# mimic1579.net
KiCad netlist of a schematic drawn in EAGLE
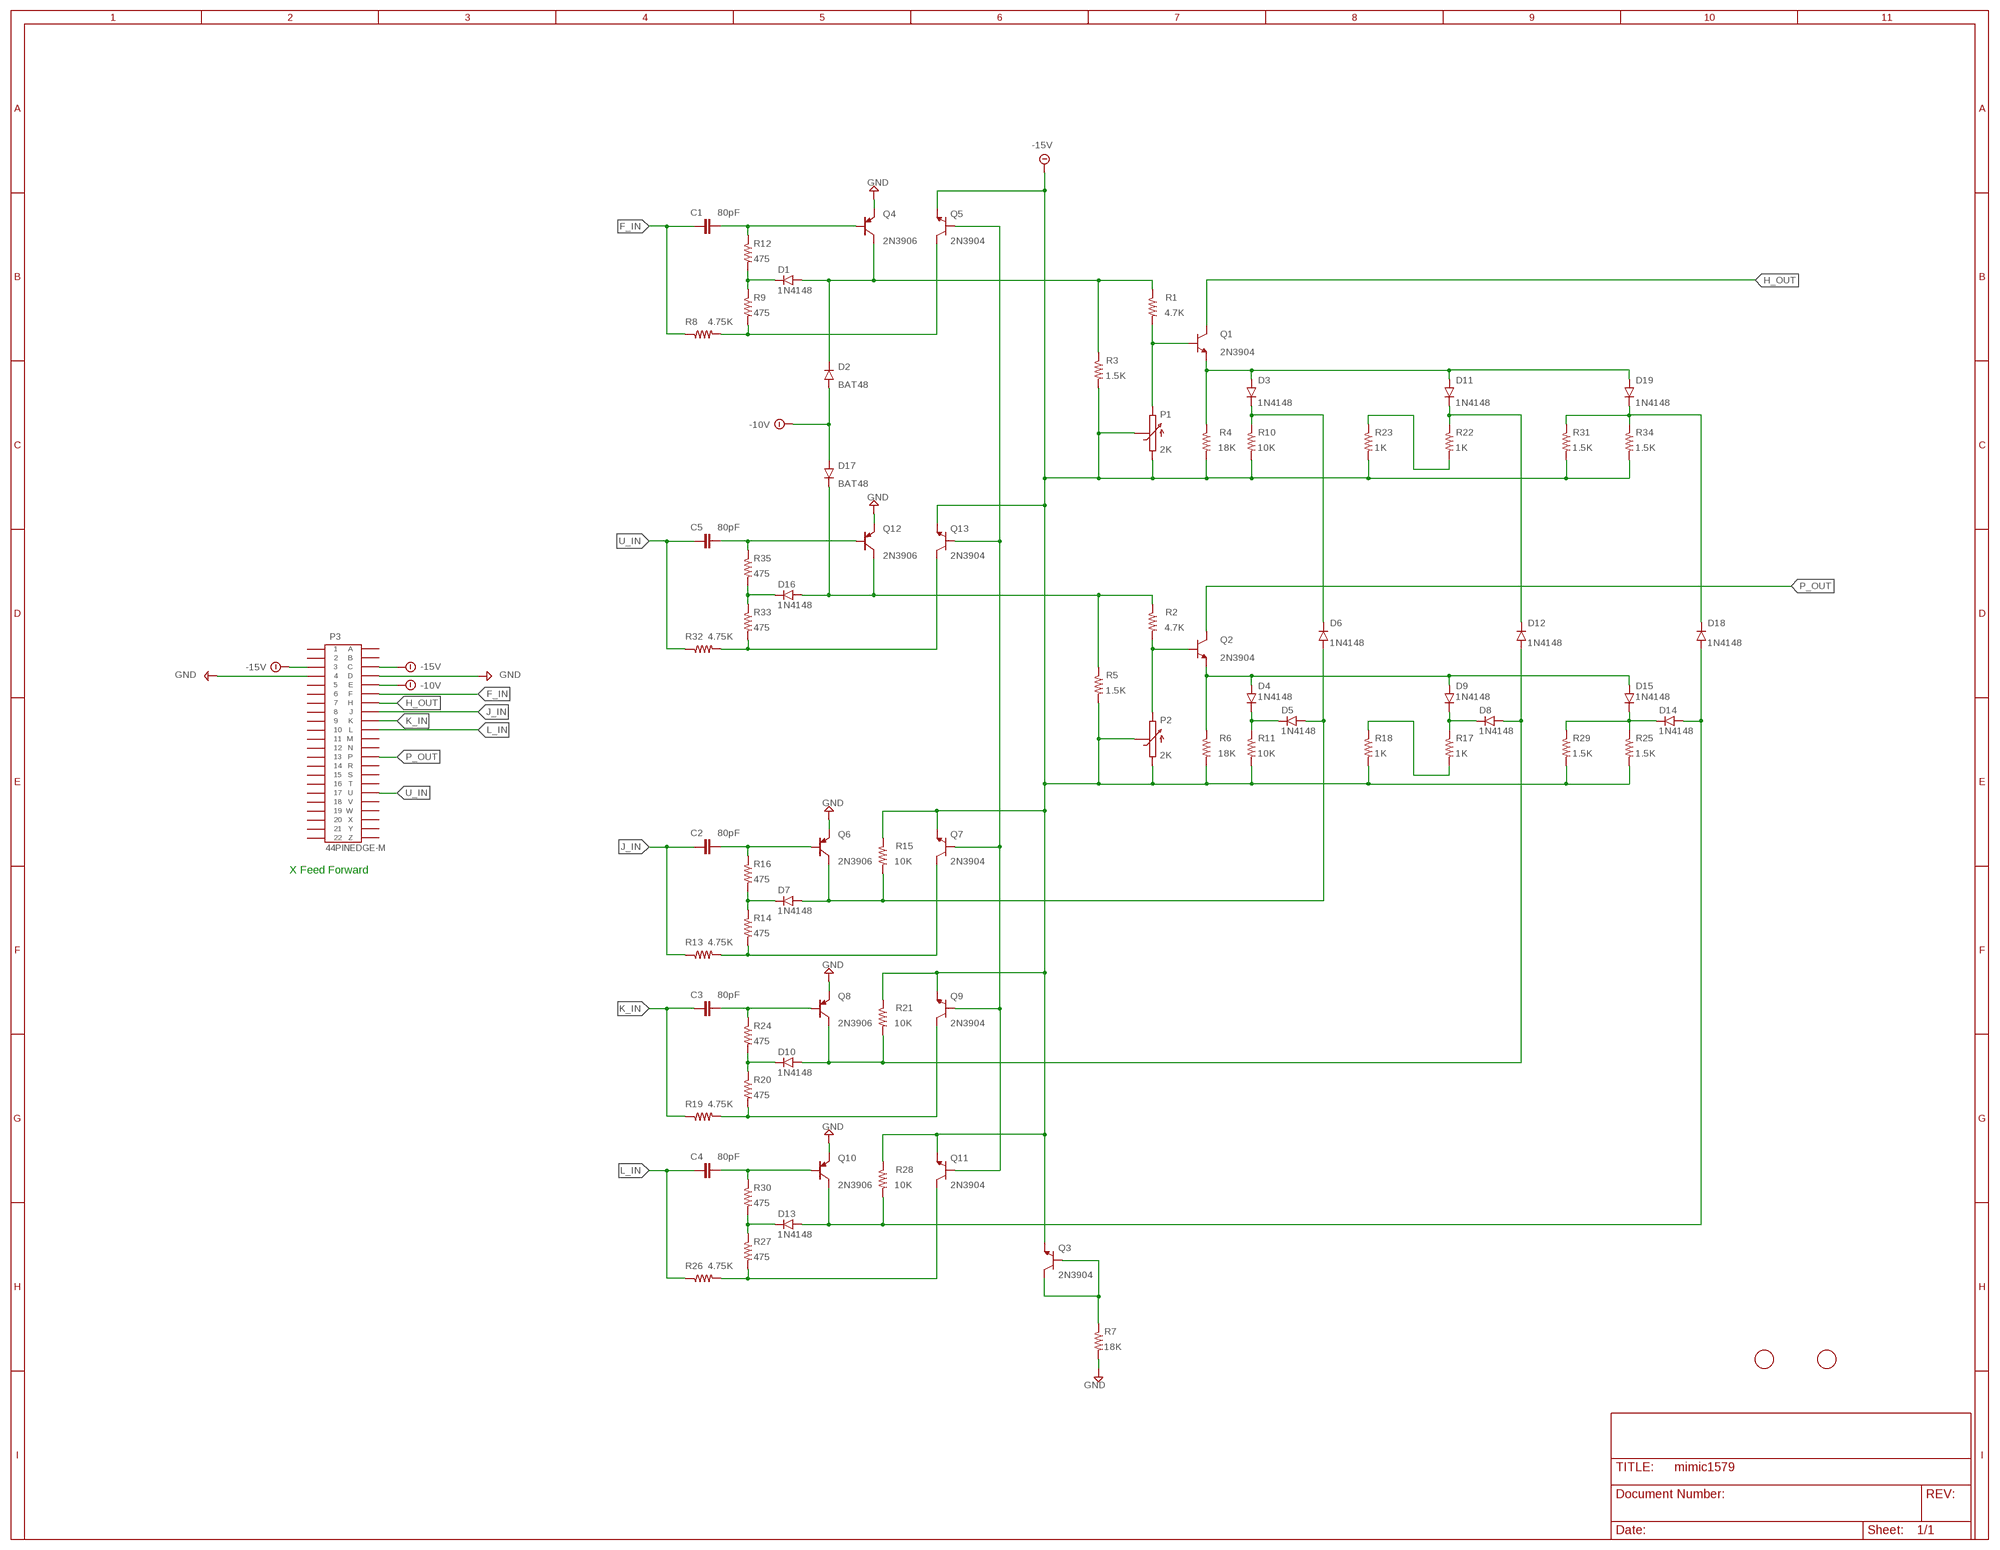
[diagram p0: schematic, sheet 1]

(export (version "E")
  (design (tool "Eeschema 10.0.6"))
  (components
    (comp (ref "C1")
      (value "80pF")
      (footprint "eagle-import:5MM_TH")
      (libsource (lib "eagle-import") (part "CAP80PF"))
    )
    (comp (ref "C2")
      (value "80pF")
      (footprint "eagle-import:5MM_TH")
      (libsource (lib "eagle-import") (part "CAP80PF"))
    )
    (comp (ref "C3")
      (value "80pF")
      (footprint "eagle-import:5MM_TH")
      (libsource (lib "eagle-import") (part "CAP80PF"))
    )
    (comp (ref "C4")
      (value "80pF")
      (footprint "eagle-import:5MM_TH")
      (libsource (lib "eagle-import") (part "CAP80PF"))
    )
    (comp (ref "C5")
      (value "80pF")
      (footprint "eagle-import:5MM_TH")
      (libsource (lib "eagle-import") (part "CAP80PF"))
    )
    (comp (ref "D1")
      (value "1N4148")
      (footprint "eagle-import:DO35-7")
      (libsource (lib "eagle-import") (part "1N4148"))
    )
    (comp (ref "D2")
      (value "BAT48")
      (footprint "eagle-import:DO35-7")
      (libsource (lib "eagle-import") (part "1N4148"))
    )
    (comp (ref "D3")
      (value "1N4148")
      (footprint "eagle-import:DO35-7")
      (libsource (lib "eagle-import") (part "1N4148"))
    )
    (comp (ref "D4")
      (value "1N4148")
      (footprint "eagle-import:DO35-7")
      (libsource (lib "eagle-import") (part "1N4148"))
    )
    (comp (ref "D5")
      (value "1N4148")
      (footprint "eagle-import:DO35-7")
      (libsource (lib "eagle-import") (part "1N4148"))
    )
    (comp (ref "D6")
      (value "1N4148")
      (footprint "eagle-import:DO35-7")
      (libsource (lib "eagle-import") (part "1N4148"))
    )
    (comp (ref "D7")
      (value "1N4148")
      (footprint "eagle-import:DO35-7")
      (libsource (lib "eagle-import") (part "1N4148"))
    )
    (comp (ref "D8")
      (value "1N4148")
      (footprint "eagle-import:DO35-7")
      (libsource (lib "eagle-import") (part "1N4148"))
    )
    (comp (ref "D9")
      (value "1N4148")
      (footprint "eagle-import:DO35-7")
      (libsource (lib "eagle-import") (part "1N4148"))
    )
    (comp (ref "D10")
      (value "1N4148")
      (footprint "eagle-import:DO35-7")
      (libsource (lib "eagle-import") (part "1N4148"))
    )
    (comp (ref "D11")
      (value "1N4148")
      (footprint "eagle-import:DO35-7")
      (libsource (lib "eagle-import") (part "1N4148"))
    )
    (comp (ref "D12")
      (value "1N4148")
      (footprint "eagle-import:DO35-7")
      (libsource (lib "eagle-import") (part "1N4148"))
    )
    (comp (ref "D13")
      (value "1N4148")
      (footprint "eagle-import:DO35-7")
      (libsource (lib "eagle-import") (part "1N4148"))
    )
    (comp (ref "D14")
      (value "1N4148")
      (footprint "eagle-import:DO35-7")
      (libsource (lib "eagle-import") (part "1N4148"))
    )
    (comp (ref "D15")
      (value "1N4148")
      (footprint "eagle-import:DO35-7")
      (libsource (lib "eagle-import") (part "1N4148"))
    )
    (comp (ref "D16")
      (value "1N4148")
      (footprint "eagle-import:DO35-7")
      (libsource (lib "eagle-import") (part "1N4148"))
    )
    (comp (ref "D17")
      (value "BAT48")
      (footprint "eagle-import:DO35-7")
      (libsource (lib "eagle-import") (part "1N4148"))
    )
    (comp (ref "D18")
      (value "1N4148")
      (footprint "eagle-import:DO35-7")
      (libsource (lib "eagle-import") (part "1N4148"))
    )
    (comp (ref "D19")
      (value "1N4148")
      (footprint "eagle-import:DO35-7")
      (libsource (lib "eagle-import") (part "1N4148"))
    )
    (comp (ref "P1")
      (value "2K")
      (footprint "eagle-import:3006P")
      (libsource (lib "eagle-import") (part "POT-3006P"))
    )
    (comp (ref "P2")
      (value "2K")
      (footprint "eagle-import:3006P")
      (libsource (lib "eagle-import") (part "POT-3006P"))
    )
    (comp (ref "P3")
      (value "44PINEDGE-M")
      (footprint "eagle-import:44PINEDGE")
      (libsource (lib "eagle-import") (part "44PINEDGE-M"))
    )
    (comp (ref "Q1")
      (value "2N3904")
      (footprint "eagle-import:TO92")
      (libsource (lib "eagle-import") (part "2N3904"))
    )
    (comp (ref "Q2")
      (value "2N3904")
      (footprint "eagle-import:TO92")
      (libsource (lib "eagle-import") (part "2N3904"))
    )
    (comp (ref "Q3")
      (value "2N3904")
      (footprint "eagle-import:TO92")
      (libsource (lib "eagle-import") (part "2N3904"))
    )
    (comp (ref "Q4")
      (value "2N3906")
      (footprint "eagle-import:TO92")
      (libsource (lib "eagle-import") (part "2N3906"))
    )
    (comp (ref "Q5")
      (value "2N3904")
      (footprint "eagle-import:TO92")
      (libsource (lib "eagle-import") (part "2N3904"))
    )
    (comp (ref "Q6")
      (value "2N3906")
      (footprint "eagle-import:TO92")
      (libsource (lib "eagle-import") (part "2N3906"))
    )
    (comp (ref "Q7")
      (value "2N3904")
      (footprint "eagle-import:TO92")
      (libsource (lib "eagle-import") (part "2N3904"))
    )
    (comp (ref "Q8")
      (value "2N3906")
      (footprint "eagle-import:TO92")
      (libsource (lib "eagle-import") (part "2N3906"))
    )
    (comp (ref "Q9")
      (value "2N3904")
      (footprint "eagle-import:TO92")
      (libsource (lib "eagle-import") (part "2N3904"))
    )
    (comp (ref "Q10")
      (value "2N3906")
      (footprint "eagle-import:TO92")
      (libsource (lib "eagle-import") (part "2N3906"))
    )
    (comp (ref "Q11")
      (value "2N3904")
      (footprint "eagle-import:TO92")
      (libsource (lib "eagle-import") (part "2N3904"))
    )
    (comp (ref "Q12")
      (value "2N3906")
      (footprint "eagle-import:TO92")
      (libsource (lib "eagle-import") (part "2N3906"))
    )
    (comp (ref "Q13")
      (value "2N3904")
      (footprint "eagle-import:TO92")
      (libsource (lib "eagle-import") (part "2N3904"))
    )
    (comp (ref "R1")
      (value "4.7K")
      (footprint "eagle-import:0207_10")
      (libsource (lib "eagle-import") (part "R-1/4WATT"))
    )
    (comp (ref "R2")
      (value "4.7K")
      (footprint "eagle-import:0207_10")
      (libsource (lib "eagle-import") (part "R-1/4WATT"))
    )
    (comp (ref "R3")
      (value "1.5K")
      (footprint "eagle-import:0207_10")
      (libsource (lib "eagle-import") (part "R-1/4WATT"))
    )
    (comp (ref "R4")
      (value "18K")
      (footprint "eagle-import:0207_10")
      (libsource (lib "eagle-import") (part "R-1/4WATT"))
    )
    (comp (ref "R5")
      (value "1.5K")
      (footprint "eagle-import:0207_10")
      (libsource (lib "eagle-import") (part "R-1/4WATT"))
    )
    (comp (ref "R6")
      (value "18K")
      (footprint "eagle-import:0207_10")
      (libsource (lib "eagle-import") (part "R-1/4WATT"))
    )
    (comp (ref "R7")
      (value "18K")
      (footprint "eagle-import:0207_10")
      (libsource (lib "eagle-import") (part "R-1/4WATT"))
    )
    (comp (ref "R8")
      (value "4.75K")
      (footprint "eagle-import:0207_10")
      (libsource (lib "eagle-import") (part "R-1/4WATT"))
    )
    (comp (ref "R9")
      (value "475")
      (footprint "eagle-import:0207_10")
      (libsource (lib "eagle-import") (part "R-1/4WATT"))
    )
    (comp (ref "R10")
      (value "10K")
      (footprint "eagle-import:0207_10")
      (libsource (lib "eagle-import") (part "R-1/4WATT"))
    )
    (comp (ref "R11")
      (value "10K")
      (footprint "eagle-import:0207_10")
      (libsource (lib "eagle-import") (part "R-1/4WATT"))
    )
    (comp (ref "R12")
      (value "475")
      (footprint "eagle-import:0207_10")
      (libsource (lib "eagle-import") (part "R-1/4WATT"))
    )
    (comp (ref "R13")
      (value "4.75K")
      (footprint "eagle-import:0207_10")
      (libsource (lib "eagle-import") (part "R-1/4WATT"))
    )
    (comp (ref "R14")
      (value "475")
      (footprint "eagle-import:0207_10")
      (libsource (lib "eagle-import") (part "R-1/4WATT"))
    )
    (comp (ref "R15")
      (value "10K")
      (footprint "eagle-import:0207_10")
      (libsource (lib "eagle-import") (part "R-1/4WATT"))
    )
    (comp (ref "R16")
      (value "475")
      (footprint "eagle-import:0207_10")
      (libsource (lib "eagle-import") (part "R-1/4WATT"))
    )
    (comp (ref "R17")
      (value "1K")
      (footprint "eagle-import:0207_10")
      (libsource (lib "eagle-import") (part "R-1/4WATT"))
    )
    (comp (ref "R18")
      (value "1K")
      (footprint "eagle-import:0207_10")
      (libsource (lib "eagle-import") (part "R-1/4WATT"))
    )
    (comp (ref "R19")
      (value "4.75K")
      (footprint "eagle-import:0207_10")
      (libsource (lib "eagle-import") (part "R-1/4WATT"))
    )
    (comp (ref "R20")
      (value "475")
      (footprint "eagle-import:0207_10")
      (libsource (lib "eagle-import") (part "R-1/4WATT"))
    )
    (comp (ref "R21")
      (value "10K")
      (footprint "eagle-import:0207_10")
      (libsource (lib "eagle-import") (part "R-1/4WATT"))
    )
    (comp (ref "R22")
      (value "1K")
      (footprint "eagle-import:0207_10")
      (libsource (lib "eagle-import") (part "R-1/4WATT"))
    )
    (comp (ref "R23")
      (value "1K")
      (footprint "eagle-import:0207_10")
      (libsource (lib "eagle-import") (part "R-1/4WATT"))
    )
    (comp (ref "R24")
      (value "475")
      (footprint "eagle-import:0207_10")
      (libsource (lib "eagle-import") (part "R-1/4WATT"))
    )
    (comp (ref "R25")
      (value "1.5K")
      (footprint "eagle-import:0207_10")
      (libsource (lib "eagle-import") (part "R-1/4WATT"))
    )
    (comp (ref "R26")
      (value "4.75K")
      (footprint "eagle-import:0207_10")
      (libsource (lib "eagle-import") (part "R-1/4WATT"))
    )
    (comp (ref "R27")
      (value "475")
      (footprint "eagle-import:0207_10")
      (libsource (lib "eagle-import") (part "R-1/4WATT"))
    )
    (comp (ref "R28")
      (value "10K")
      (footprint "eagle-import:0207_10")
      (libsource (lib "eagle-import") (part "R-1/4WATT"))
    )
    (comp (ref "R29")
      (value "1.5K")
      (footprint "eagle-import:0207_10")
      (libsource (lib "eagle-import") (part "R-1/4WATT"))
    )
    (comp (ref "R30")
      (value "475")
      (footprint "eagle-import:0207_10")
      (libsource (lib "eagle-import") (part "R-1/4WATT"))
    )
    (comp (ref "R31")
      (value "1.5K")
      (footprint "eagle-import:0207_10")
      (libsource (lib "eagle-import") (part "R-1/4WATT"))
    )
    (comp (ref "R32")
      (value "4.75K")
      (footprint "eagle-import:0207_10")
      (libsource (lib "eagle-import") (part "R-1/4WATT"))
    )
    (comp (ref "R33")
      (value "475")
      (footprint "eagle-import:0207_10")
      (libsource (lib "eagle-import") (part "R-1/4WATT"))
    )
    (comp (ref "R34")
      (value "1.5K")
      (footprint "eagle-import:0207_10")
      (libsource (lib "eagle-import") (part "R-1/4WATT"))
    )
    (comp (ref "R35")
      (value "475")
      (footprint "eagle-import:0207_10")
      (libsource (lib "eagle-import") (part "R-1/4WATT"))
    )
    (comp (ref "U$1")
      (value "FIDUCIAL")
      (footprint "eagle-import:FIDUCIAL_1MM")
      (libsource (lib "eagle-import") (part "FIDUCIAL"))
    )
    (comp (ref "U$2")
      (value "FIDUCIAL")
      (footprint "eagle-import:FIDUCIAL_1MM")
      (libsource (lib "eagle-import") (part "FIDUCIAL"))
    )
  )
  (nets
    (net (code "1") (name "-10V") (class "Default")
      (node (ref "D17") (pin "A") (pinfunction "A_A") (pintype "passive"))
      (node (ref "D2") (pin "A") (pinfunction "A_A") (pintype "passive"))
      (node (ref "P3") (pin "E") (pinfunction "E_E") (pintype "passive"))
    )
    (net (code "2") (name "-15V") (class "Default")
      (node (ref "P1") (pin "1") (pinfunction "1_1") (pintype "passive"))
      (node (ref "P1") (pin "2") (pinfunction "2_2") (pintype "passive"))
      (node (ref "P2") (pin "1") (pinfunction "1_1") (pintype "passive"))
      (node (ref "P2") (pin "2") (pinfunction "2_2") (pintype "passive"))
      (node (ref "P3") (pin "3") (pinfunction "3_3") (pintype "passive"))
      (node (ref "P3") (pin "C") (pinfunction "C_C") (pintype "passive"))
      (node (ref "Q11") (pin "1") (pinfunction "E_1") (pintype "passive"))
      (node (ref "Q13") (pin "1") (pinfunction "E_1") (pintype "passive"))
      (node (ref "Q3") (pin "1") (pinfunction "E_1") (pintype "passive"))
      (node (ref "Q5") (pin "1") (pinfunction "E_1") (pintype "passive"))
      (node (ref "Q7") (pin "1") (pinfunction "E_1") (pintype "passive"))
      (node (ref "Q9") (pin "1") (pinfunction "E_1") (pintype "passive"))
      (node (ref "R10") (pin "2") (pinfunction "P$2_2") (pintype "passive"))
      (node (ref "R11") (pin "2") (pinfunction "P$2_2") (pintype "passive"))
      (node (ref "R15") (pin "1") (pinfunction "P$1_1") (pintype "passive"))
      (node (ref "R18") (pin "2") (pinfunction "P$2_2") (pintype "passive"))
      (node (ref "R21") (pin "1") (pinfunction "P$1_1") (pintype "passive"))
      (node (ref "R23") (pin "2") (pinfunction "P$2_2") (pintype "passive"))
      (node (ref "R25") (pin "2") (pinfunction "P$2_2") (pintype "passive"))
      (node (ref "R28") (pin "1") (pinfunction "P$1_1") (pintype "passive"))
      (node (ref "R29") (pin "2") (pinfunction "P$2_2") (pintype "passive"))
      (node (ref "R3") (pin "2") (pinfunction "P$2_2") (pintype "passive"))
      (node (ref "R31") (pin "2") (pinfunction "P$2_2") (pintype "passive"))
      (node (ref "R34") (pin "2") (pinfunction "P$2_2") (pintype "passive"))
      (node (ref "R4") (pin "2") (pinfunction "P$2_2") (pintype "passive"))
      (node (ref "R5") (pin "2") (pinfunction "P$2_2") (pintype "passive"))
      (node (ref "R6") (pin "2") (pinfunction "P$2_2") (pintype "passive"))
    )
    (net (code "3") (name "F_IN") (class "Default")
      (node (ref "C1") (pin "1") (pinfunction "1_1") (pintype "passive"))
      (node (ref "P3") (pin "F") (pinfunction "F_F") (pintype "passive"))
      (node (ref "R8") (pin "1") (pinfunction "P$1_1") (pintype "passive"))
    )
    (net (code "4") (name "GND") (class "Default")
      (node (ref "P3") (pin "4") (pinfunction "4_4") (pintype "passive"))
      (node (ref "P3") (pin "D") (pinfunction "D_D") (pintype "passive"))
      (node (ref "Q10") (pin "3") (pinfunction "E_3") (pintype "passive"))
      (node (ref "Q12") (pin "3") (pinfunction "E_3") (pintype "passive"))
      (node (ref "Q4") (pin "3") (pinfunction "E_3") (pintype "passive"))
      (node (ref "Q6") (pin "3") (pinfunction "E_3") (pintype "passive"))
      (node (ref "Q8") (pin "3") (pinfunction "E_3") (pintype "passive"))
      (node (ref "R7") (pin "2") (pinfunction "P$2_2") (pintype "passive"))
    )
    (net (code "5") (name "H_OUT") (class "Default")
      (node (ref "P3") (pin "H") (pinfunction "H_H") (pintype "passive"))
      (node (ref "Q1") (pin "3") (pinfunction "C_3") (pintype "passive"))
    )
    (net (code "6") (name "J_IN") (class "Default")
      (node (ref "C2") (pin "1") (pinfunction "1_1") (pintype "passive"))
      (node (ref "P3") (pin "J") (pinfunction "J_J") (pintype "passive"))
      (node (ref "R13") (pin "1") (pinfunction "P$1_1") (pintype "passive"))
    )
    (net (code "7") (name "K_IN") (class "Default")
      (node (ref "C3") (pin "1") (pinfunction "1_1") (pintype "passive"))
      (node (ref "P3") (pin "K") (pinfunction "K_K") (pintype "passive"))
      (node (ref "R19") (pin "1") (pinfunction "P$1_1") (pintype "passive"))
    )
    (net (code "8") (name "L_IN") (class "Default")
      (node (ref "C4") (pin "1") (pinfunction "1_1") (pintype "passive"))
      (node (ref "P3") (pin "L") (pinfunction "L_L") (pintype "passive"))
      (node (ref "R26") (pin "1") (pinfunction "P$1_1") (pintype "passive"))
    )
    (net (code "9") (name "Net-(Q1-B)") (class "Default")
      (node (ref "P1") (pin "3") (pinfunction "3_3") (pintype "passive"))
      (node (ref "Q1") (pin "2") (pinfunction "B_2") (pintype "passive"))
      (node (ref "R1") (pin "2") (pinfunction "P$2_2") (pintype "passive"))
    )
    (net (code "10") (name "Net-(Q1-E)") (class "Default")
      (node (ref "D11") (pin "A") (pinfunction "A_A") (pintype "passive"))
      (node (ref "D19") (pin "A") (pinfunction "A_A") (pintype "passive"))
      (node (ref "D3") (pin "A") (pinfunction "A_A") (pintype "passive"))
      (node (ref "Q1") (pin "1") (pinfunction "E_1") (pintype "passive"))
      (node (ref "R4") (pin "1") (pinfunction "P$1_1") (pintype "passive"))
    )
    (net (code "11") (name "Net-(Q2-B)") (class "Default")
      (node (ref "P2") (pin "3") (pinfunction "3_3") (pintype "passive"))
      (node (ref "Q2") (pin "2") (pinfunction "B_2") (pintype "passive"))
      (node (ref "R2") (pin "2") (pinfunction "P$2_2") (pintype "passive"))
    )
    (net (code "12") (name "Net-(Q2-E)") (class "Default")
      (node (ref "D15") (pin "A") (pinfunction "A_A") (pintype "passive"))
      (node (ref "D4") (pin "A") (pinfunction "A_A") (pintype "passive"))
      (node (ref "D9") (pin "A") (pinfunction "A_A") (pintype "passive"))
      (node (ref "Q2") (pin "1") (pinfunction "E_1") (pintype "passive"))
      (node (ref "R6") (pin "1") (pinfunction "P$1_1") (pintype "passive"))
    )
    (net (code "13") (name "Net-(Q3-B)") (class "Default")
      (node (ref "Q3") (pin "2") (pinfunction "B_2") (pintype "passive"))
      (node (ref "Q3") (pin "3") (pinfunction "C_3") (pintype "passive"))
      (node (ref "R7") (pin "1") (pinfunction "P$1_1") (pintype "passive"))
    )
    (net (code "14") (name "Net-(Q4-B)") (class "Default")
      (node (ref "C1") (pin "2") (pinfunction "2_2") (pintype "passive"))
      (node (ref "Q4") (pin "2") (pinfunction "B_2") (pintype "passive"))
      (node (ref "R12") (pin "1") (pinfunction "P$1_1") (pintype "passive"))
    )
    (net (code "15") (name "Net-(Q4-C)") (class "Default")
      (node (ref "D1") (pin "A") (pinfunction "A_A") (pintype "passive"))
      (node (ref "D2") (pin "C") (pinfunction "C_C") (pintype "passive"))
      (node (ref "Q4") (pin "1") (pinfunction "C_1") (pintype "passive"))
      (node (ref "R1") (pin "1") (pinfunction "P$1_1") (pintype "passive"))
      (node (ref "R3") (pin "1") (pinfunction "P$1_1") (pintype "passive"))
    )
    (net (code "16") (name "Net-(Q5-C)") (class "Default")
      (node (ref "Q5") (pin "3") (pinfunction "C_3") (pintype "passive"))
      (node (ref "R8") (pin "2") (pinfunction "P$2_2") (pintype "passive"))
      (node (ref "R9") (pin "2") (pinfunction "P$2_2") (pintype "passive"))
    )
    (net (code "17") (name "Net-(Q6-B)") (class "Default")
      (node (ref "C2") (pin "2") (pinfunction "2_2") (pintype "passive"))
      (node (ref "Q6") (pin "2") (pinfunction "B_2") (pintype "passive"))
      (node (ref "R16") (pin "1") (pinfunction "P$1_1") (pintype "passive"))
    )
    (net (code "18") (name "Net-(Q6-C)") (class "Default")
      (node (ref "D5") (pin "A") (pinfunction "A_A") (pintype "passive"))
      (node (ref "D6") (pin "A") (pinfunction "A_A") (pintype "passive"))
      (node (ref "D7") (pin "A") (pinfunction "A_A") (pintype "passive"))
      (node (ref "Q6") (pin "1") (pinfunction "C_1") (pintype "passive"))
      (node (ref "R15") (pin "2") (pinfunction "P$2_2") (pintype "passive"))
    )
    (net (code "19") (name "Net-(Q7-C)") (class "Default")
      (node (ref "Q7") (pin "3") (pinfunction "C_3") (pintype "passive"))
      (node (ref "R13") (pin "2") (pinfunction "P$2_2") (pintype "passive"))
      (node (ref "R14") (pin "2") (pinfunction "P$2_2") (pintype "passive"))
    )
    (net (code "20") (name "Net-(Q8-B)") (class "Default")
      (node (ref "C3") (pin "2") (pinfunction "2_2") (pintype "passive"))
      (node (ref "Q8") (pin "2") (pinfunction "B_2") (pintype "passive"))
      (node (ref "R24") (pin "1") (pinfunction "P$1_1") (pintype "passive"))
    )
    (net (code "21") (name "Net-(Q8-C)") (class "Default")
      (node (ref "D10") (pin "A") (pinfunction "A_A") (pintype "passive"))
      (node (ref "D12") (pin "A") (pinfunction "A_A") (pintype "passive"))
      (node (ref "D8") (pin "A") (pinfunction "A_A") (pintype "passive"))
      (node (ref "Q8") (pin "1") (pinfunction "C_1") (pintype "passive"))
      (node (ref "R21") (pin "2") (pinfunction "P$2_2") (pintype "passive"))
    )
    (net (code "22") (name "Net-(Q9-C)") (class "Default")
      (node (ref "Q9") (pin "3") (pinfunction "C_3") (pintype "passive"))
      (node (ref "R19") (pin "2") (pinfunction "P$2_2") (pintype "passive"))
      (node (ref "R20") (pin "2") (pinfunction "P$2_2") (pintype "passive"))
    )
    (net (code "23") (name "Net-(Q10-B)") (class "Default")
      (node (ref "C4") (pin "2") (pinfunction "2_2") (pintype "passive"))
      (node (ref "Q10") (pin "2") (pinfunction "B_2") (pintype "passive"))
      (node (ref "R30") (pin "1") (pinfunction "P$1_1") (pintype "passive"))
    )
    (net (code "24") (name "Net-(Q10-C)") (class "Default")
      (node (ref "D13") (pin "A") (pinfunction "A_A") (pintype "passive"))
      (node (ref "D14") (pin "A") (pinfunction "A_A") (pintype "passive"))
      (node (ref "D18") (pin "A") (pinfunction "A_A") (pintype "passive"))
      (node (ref "Q10") (pin "1") (pinfunction "C_1") (pintype "passive"))
      (node (ref "R28") (pin "2") (pinfunction "P$2_2") (pintype "passive"))
    )
    (net (code "25") (name "Net-(Q11-B)") (class "Default")
      (node (ref "Q11") (pin "2") (pinfunction "B_2") (pintype "passive"))
      (node (ref "Q13") (pin "2") (pinfunction "B_2") (pintype "passive"))
      (node (ref "Q5") (pin "2") (pinfunction "B_2") (pintype "passive"))
      (node (ref "Q7") (pin "2") (pinfunction "B_2") (pintype "passive"))
      (node (ref "Q9") (pin "2") (pinfunction "B_2") (pintype "passive"))
    )
    (net (code "26") (name "Net-(Q11-C)") (class "Default")
      (node (ref "Q11") (pin "3") (pinfunction "C_3") (pintype "passive"))
      (node (ref "R26") (pin "2") (pinfunction "P$2_2") (pintype "passive"))
      (node (ref "R27") (pin "2") (pinfunction "P$2_2") (pintype "passive"))
    )
    (net (code "27") (name "Net-(Q12-B)") (class "Default")
      (node (ref "C5") (pin "2") (pinfunction "2_2") (pintype "passive"))
      (node (ref "Q12") (pin "2") (pinfunction "B_2") (pintype "passive"))
      (node (ref "R35") (pin "1") (pinfunction "P$1_1") (pintype "passive"))
    )
    (net (code "28") (name "Net-(Q12-C)") (class "Default")
      (node (ref "D16") (pin "A") (pinfunction "A_A") (pintype "passive"))
      (node (ref "D17") (pin "C") (pinfunction "C_C") (pintype "passive"))
      (node (ref "Q12") (pin "1") (pinfunction "C_1") (pintype "passive"))
      (node (ref "R2") (pin "1") (pinfunction "P$1_1") (pintype "passive"))
      (node (ref "R5") (pin "1") (pinfunction "P$1_1") (pintype "passive"))
    )
    (net (code "29") (name "Net-(Q13-C)") (class "Default")
      (node (ref "Q13") (pin "3") (pinfunction "C_3") (pintype "passive"))
      (node (ref "R32") (pin "2") (pinfunction "P$2_2") (pintype "passive"))
      (node (ref "R33") (pin "2") (pinfunction "P$2_2") (pintype "passive"))
    )
    (net (code "30") (name "Net-(R10-P$1)") (class "Default")
      (node (ref "D3") (pin "C") (pinfunction "C_C") (pintype "passive"))
      (node (ref "D6") (pin "C") (pinfunction "C_C") (pintype "passive"))
      (node (ref "R10") (pin "1") (pinfunction "P$1_1") (pintype "passive"))
    )
    (net (code "31") (name "Net-(R11-P$1)") (class "Default")
      (node (ref "D4") (pin "C") (pinfunction "C_C") (pintype "passive"))
      (node (ref "D5") (pin "C") (pinfunction "C_C") (pintype "passive"))
      (node (ref "R11") (pin "1") (pinfunction "P$1_1") (pintype "passive"))
    )
    (net (code "32") (name "Net-(R12-P$2)") (class "Default")
      (node (ref "D1") (pin "C") (pinfunction "C_C") (pintype "passive"))
      (node (ref "R12") (pin "2") (pinfunction "P$2_2") (pintype "passive"))
      (node (ref "R9") (pin "1") (pinfunction "P$1_1") (pintype "passive"))
    )
    (net (code "33") (name "Net-(R14-P$1)") (class "Default")
      (node (ref "D7") (pin "C") (pinfunction "C_C") (pintype "passive"))
      (node (ref "R14") (pin "1") (pinfunction "P$1_1") (pintype "passive"))
      (node (ref "R16") (pin "2") (pinfunction "P$2_2") (pintype "passive"))
    )
    (net (code "34") (name "Net-(R17-P$1)") (class "Default")
      (node (ref "D8") (pin "C") (pinfunction "C_C") (pintype "passive"))
      (node (ref "D9") (pin "C") (pinfunction "C_C") (pintype "passive"))
      (node (ref "R17") (pin "1") (pinfunction "P$1_1") (pintype "passive"))
    )
    (net (code "35") (name "Net-(R17-P$2)") (class "Default")
      (node (ref "R17") (pin "2") (pinfunction "P$2_2") (pintype "passive"))
      (node (ref "R18") (pin "1") (pinfunction "P$1_1") (pintype "passive"))
    )
    (net (code "36") (name "Net-(R20-P$1)") (class "Default")
      (node (ref "D10") (pin "C") (pinfunction "C_C") (pintype "passive"))
      (node (ref "R20") (pin "1") (pinfunction "P$1_1") (pintype "passive"))
      (node (ref "R24") (pin "2") (pinfunction "P$2_2") (pintype "passive"))
    )
    (net (code "37") (name "Net-(R22-P$1)") (class "Default")
      (node (ref "D11") (pin "C") (pinfunction "C_C") (pintype "passive"))
      (node (ref "D12") (pin "C") (pinfunction "C_C") (pintype "passive"))
      (node (ref "R22") (pin "1") (pinfunction "P$1_1") (pintype "passive"))
    )
    (net (code "38") (name "Net-(R22-P$2)") (class "Default")
      (node (ref "R22") (pin "2") (pinfunction "P$2_2") (pintype "passive"))
      (node (ref "R23") (pin "1") (pinfunction "P$1_1") (pintype "passive"))
    )
    (net (code "39") (name "Net-(R25-P$1)") (class "Default")
      (node (ref "D14") (pin "C") (pinfunction "C_C") (pintype "passive"))
      (node (ref "D15") (pin "C") (pinfunction "C_C") (pintype "passive"))
      (node (ref "R25") (pin "1") (pinfunction "P$1_1") (pintype "passive"))
      (node (ref "R29") (pin "1") (pinfunction "P$1_1") (pintype "passive"))
    )
    (net (code "40") (name "Net-(R27-P$1)") (class "Default")
      (node (ref "D13") (pin "C") (pinfunction "C_C") (pintype "passive"))
      (node (ref "R27") (pin "1") (pinfunction "P$1_1") (pintype "passive"))
      (node (ref "R30") (pin "2") (pinfunction "P$2_2") (pintype "passive"))
    )
    (net (code "41") (name "Net-(R31-P$1)") (class "Default")
      (node (ref "D18") (pin "C") (pinfunction "C_C") (pintype "passive"))
      (node (ref "D19") (pin "C") (pinfunction "C_C") (pintype "passive"))
      (node (ref "R31") (pin "1") (pinfunction "P$1_1") (pintype "passive"))
      (node (ref "R34") (pin "1") (pinfunction "P$1_1") (pintype "passive"))
    )
    (net (code "42") (name "Net-(R33-P$1)") (class "Default")
      (node (ref "D16") (pin "C") (pinfunction "C_C") (pintype "passive"))
      (node (ref "R33") (pin "1") (pinfunction "P$1_1") (pintype "passive"))
      (node (ref "R35") (pin "2") (pinfunction "P$2_2") (pintype "passive"))
    )
    (net (code "43") (name "P_OUT") (class "Default")
      (node (ref "P3") (pin "P") (pinfunction "P_P") (pintype "passive"))
      (node (ref "Q2") (pin "3") (pinfunction "C_3") (pintype "passive"))
    )
    (net (code "44") (name "U_IN") (class "Default")
      (node (ref "C5") (pin "1") (pinfunction "1_1") (pintype "passive"))
      (node (ref "P3") (pin "U") (pinfunction "U_U") (pintype "passive"))
      (node (ref "R32") (pin "1") (pinfunction "P$1_1") (pintype "passive"))
    )
    (net (code "45") (name "unconnected-(P3-Pad1)") (class "Default")
      (node (ref "P3") (pin "1") (pinfunction "1_1") (pintype "passive"))
    )
    (net (code "46") (name "unconnected-(P3-Pad2)") (class "Default")
      (node (ref "P3") (pin "2") (pinfunction "2_2") (pintype "passive"))
    )
    (net (code "47") (name "unconnected-(P3-Pad5)") (class "Default")
      (node (ref "P3") (pin "5") (pinfunction "5_5") (pintype "passive"))
    )
    (net (code "48") (name "unconnected-(P3-Pad6)") (class "Default")
      (node (ref "P3") (pin "6") (pinfunction "6_6") (pintype "passive"))
    )
    (net (code "49") (name "unconnected-(P3-Pad7)") (class "Default")
      (node (ref "P3") (pin "7") (pinfunction "7_7") (pintype "passive"))
    )
    (net (code "50") (name "unconnected-(P3-Pad8)") (class "Default")
      (node (ref "P3") (pin "8") (pinfunction "8_8") (pintype "passive"))
    )
    (net (code "51") (name "unconnected-(P3-Pad9)") (class "Default")
      (node (ref "P3") (pin "9") (pinfunction "9_9") (pintype "passive"))
    )
    (net (code "52") (name "unconnected-(P3-Pad10)") (class "Default")
      (node (ref "P3") (pin "10") (pinfunction "10_10") (pintype "passive"))
    )
    (net (code "53") (name "unconnected-(P3-Pad11)") (class "Default")
      (node (ref "P3") (pin "11") (pinfunction "11_11") (pintype "passive"))
    )
    (net (code "54") (name "unconnected-(P3-Pad12)") (class "Default")
      (node (ref "P3") (pin "12") (pinfunction "12_12") (pintype "passive"))
    )
    (net (code "55") (name "unconnected-(P3-Pad13)") (class "Default")
      (node (ref "P3") (pin "13") (pinfunction "13_13") (pintype "passive"))
    )
    (net (code "56") (name "unconnected-(P3-Pad14)") (class "Default")
      (node (ref "P3") (pin "14") (pinfunction "14_14") (pintype "passive"))
    )
    (net (code "57") (name "unconnected-(P3-Pad15)") (class "Default")
      (node (ref "P3") (pin "15") (pinfunction "15_15") (pintype "passive"))
    )
    (net (code "58") (name "unconnected-(P3-Pad16)") (class "Default")
      (node (ref "P3") (pin "16") (pinfunction "16_16") (pintype "passive"))
    )
    (net (code "59") (name "unconnected-(P3-Pad17)") (class "Default")
      (node (ref "P3") (pin "17") (pinfunction "17_17") (pintype "passive"))
    )
    (net (code "60") (name "unconnected-(P3-Pad18)") (class "Default")
      (node (ref "P3") (pin "18") (pinfunction "18_18") (pintype "passive"))
    )
    (net (code "61") (name "unconnected-(P3-Pad19)") (class "Default")
      (node (ref "P3") (pin "19") (pinfunction "19_19") (pintype "passive"))
    )
    (net (code "62") (name "unconnected-(P3-Pad20)") (class "Default")
      (node (ref "P3") (pin "20") (pinfunction "20_20") (pintype "passive"))
    )
    (net (code "63") (name "unconnected-(P3-Pad21)") (class "Default")
      (node (ref "P3") (pin "21") (pinfunction "21_21") (pintype "passive"))
    )
    (net (code "64") (name "unconnected-(P3-Pad22)") (class "Default")
      (node (ref "P3") (pin "22") (pinfunction "22_22") (pintype "passive"))
    )
    (net (code "65") (name "unconnected-(P3-PadA)") (class "Default")
      (node (ref "P3") (pin "A") (pinfunction "A_A") (pintype "passive"))
    )
    (net (code "66") (name "unconnected-(P3-PadB)") (class "Default")
      (node (ref "P3") (pin "B") (pinfunction "B_B") (pintype "passive"))
    )
    (net (code "67") (name "unconnected-(P3-PadM)") (class "Default")
      (node (ref "P3") (pin "M") (pinfunction "M_M") (pintype "passive"))
    )
    (net (code "68") (name "unconnected-(P3-PadN)") (class "Default")
      (node (ref "P3") (pin "N") (pinfunction "N_N") (pintype "passive"))
    )
    (net (code "69") (name "unconnected-(P3-PadR)") (class "Default")
      (node (ref "P3") (pin "R") (pinfunction "R_R") (pintype "passive"))
    )
    (net (code "70") (name "unconnected-(P3-PadS)") (class "Default")
      (node (ref "P3") (pin "S") (pinfunction "S_S") (pintype "passive"))
    )
    (net (code "71") (name "unconnected-(P3-PadT)") (class "Default")
      (node (ref "P3") (pin "T") (pinfunction "T_T") (pintype "passive"))
    )
    (net (code "72") (name "unconnected-(P3-PadV)") (class "Default")
      (node (ref "P3") (pin "V") (pinfunction "V_V") (pintype "passive"))
    )
    (net (code "73") (name "unconnected-(P3-PadW)") (class "Default")
      (node (ref "P3") (pin "W") (pinfunction "W_W") (pintype "passive"))
    )
    (net (code "74") (name "unconnected-(P3-PadX)") (class "Default")
      (node (ref "P3") (pin "X") (pinfunction "X_X") (pintype "passive"))
    )
    (net (code "75") (name "unconnected-(P3-PadY)") (class "Default")
      (node (ref "P3") (pin "Y") (pinfunction "Y_Y") (pintype "passive"))
    )
    (net (code "76") (name "unconnected-(P3-PadZ)") (class "Default")
      (node (ref "P3") (pin "Z") (pinfunction "Z_Z") (pintype "passive"))
    )
  )
)
